# BBiQ-1_0.net
KiCad netlist of a schematic drawn in EAGLE
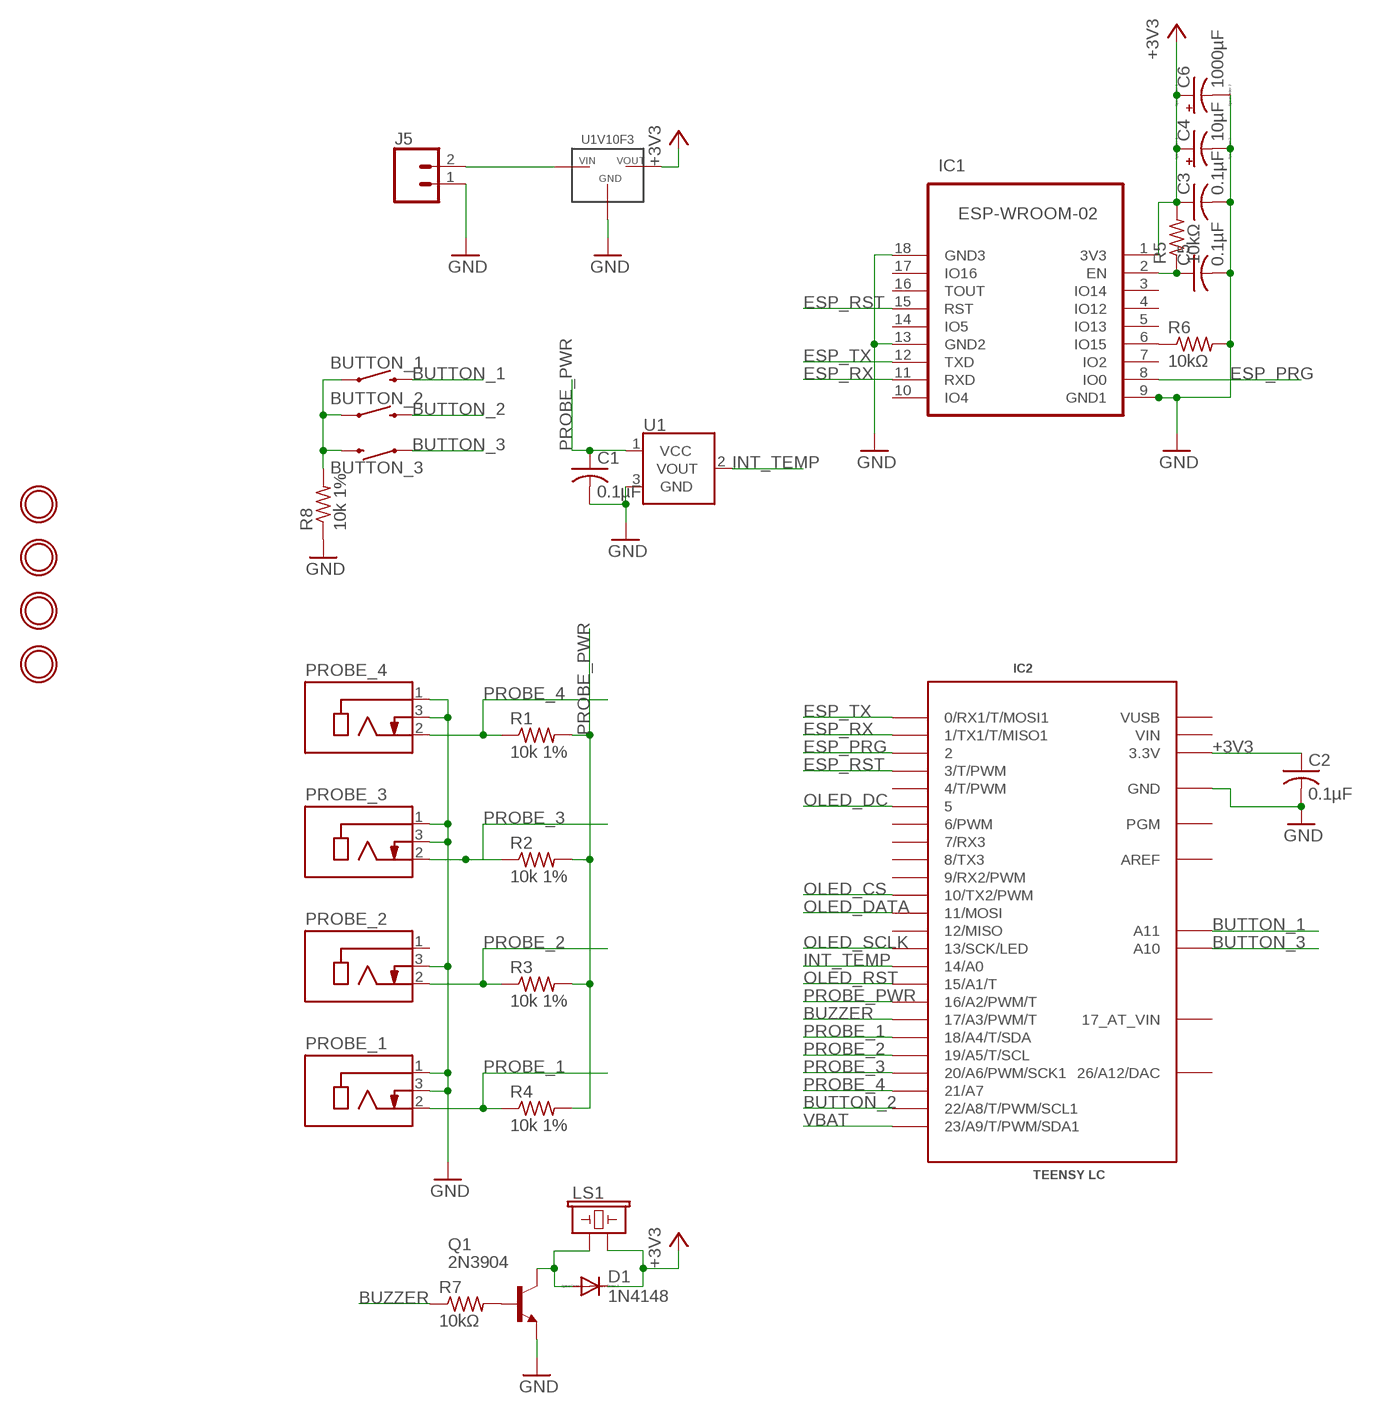
[diagram p0: schematic, sheet 1]

(export (version "E")
  (design (tool "Eeschema 10.0.6"))
  (components
    (comp (ref "BUTTON_1")
      (value "MOMENTARY-SWITCH-SPST-PTH-6.0MM")
      (footprint "eagle-import:TACTILE_SWITCH_PTH_6.0MM")
      (libsource (lib "eagle-import") (part "MOMENTARY-SWITCH-SPST-PTH-6.0MM"))
    )
    (comp (ref "BUTTON_2")
      (value "MOMENTARY-SWITCH-SPST-PTH-6.0MM")
      (footprint "eagle-import:TACTILE_SWITCH_PTH_6.0MM")
      (libsource (lib "eagle-import") (part "MOMENTARY-SWITCH-SPST-PTH-6.0MM"))
    )
    (comp (ref "BUTTON_3")
      (value "MOMENTARY-SWITCH-SPST-PTH-6.0MM")
      (footprint "eagle-import:TACTILE_SWITCH_PTH_6.0MM")
      (libsource (lib "eagle-import") (part "MOMENTARY-SWITCH-SPST-PTH-6.0MM"))
    )
    (comp (ref "C1")
      (value "0.1µF")
      (footprint "eagle-import:C025-025X050")
      (libsource (lib "eagle-import") (part "C-US025-025X050"))
    )
    (comp (ref "C2")
      (value "0.1µF")
      (footprint "eagle-import:C025-025X050")
      (libsource (lib "eagle-import") (part "C-US025-025X050"))
    )
    (comp (ref "C3")
      (value "0.1µF")
      (footprint "eagle-import:C025-025X050")
      (libsource (lib "eagle-import") (part "C-US025-025X050"))
    )
    (comp (ref "C4")
      (value "10µF")
      (footprint "eagle-import:E2-5")
      (libsource (lib "eagle-import") (part "CPOL-USE2-5"))
    )
    (comp (ref "C5")
      (value "0.1µF")
      (footprint "eagle-import:C025-025X050")
      (libsource (lib "eagle-import") (part "C-US025-025X050"))
    )
    (comp (ref "C6")
      (value "1000µF")
      (footprint "eagle-import:E3,5-8")
      (libsource (lib "eagle-import") (part "CPOL-USE3.5-8"))
    )
    (comp (ref "D1")
      (value "1N4148")
      (footprint "eagle-import:DO35-7")
      (libsource (lib "eagle-import") (part "1N4148DO35-7"))
    )
    (comp (ref "IC1")
      (value "ESP-WROOM-02")
      (footprint "eagle-import:ESP-WROOM-02")
      (libsource (lib "eagle-import") (part "ESP-WROOM-02"))
    )
    (comp (ref "IC2")
      (value "TEENSY LC")
      (footprint "eagle-import:TEENSY_3.0-3.2&LC_ALL_PINS")
      (libsource (lib "eagle-import") (part "TEENSY_LC_ALL_PINS"))
    )
    (comp (ref "J5")
      (value "CONN_02JST-PTH-2")
      (footprint "eagle-import:JST-2-PTH")
      (libsource (lib "eagle-import") (part "CONN_02JST-PTH-2"))
    )
    (comp (ref "LS1")
      (value "BUZZER-PTH")
      (footprint "eagle-import:BUZZER-12MM")
      (libsource (lib "eagle-import") (part "BUZZER-PTH"))
    )
    (comp (ref "PROBE_1")
      (value "MJ-2506N")
      (footprint "eagle-import:CUI_MJ-2506N")
      (fields (field (name "MANUFACTURER") "CUI INC"))
      (libsource (lib "eagle-import") (part "MJ-2506N"))
    )
    (comp (ref "PROBE_2")
      (value "MJ-2506N")
      (footprint "eagle-import:CUI_MJ-2506N")
      (fields (field (name "MANUFACTURER") "CUI INC"))
      (libsource (lib "eagle-import") (part "MJ-2506N"))
    )
    (comp (ref "PROBE_3")
      (value "MJ-2506N")
      (footprint "eagle-import:CUI_MJ-2506N")
      (fields (field (name "MANUFACTURER") "CUI INC"))
      (libsource (lib "eagle-import") (part "MJ-2506N"))
    )
    (comp (ref "PROBE_4")
      (value "MJ-2506N")
      (footprint "eagle-import:CUI_MJ-2506N")
      (fields (field (name "MANUFACTURER") "CUI INC"))
      (libsource (lib "eagle-import") (part "MJ-2506N"))
    )
    (comp (ref "Q1")
      (value "2N3904")
      (footprint "eagle-import:TO92")
      (libsource (lib "eagle-import") (part "2N3904"))
    )
    (comp (ref "R1")
      (value "10k 1%")
      (footprint "eagle-import:0207_7")
      (libsource (lib "eagle-import") (part "R-US_0207/7"))
    )
    (comp (ref "R2")
      (value "10k 1%")
      (footprint "eagle-import:0207_7")
      (libsource (lib "eagle-import") (part "R-US_0207/7"))
    )
    (comp (ref "R3")
      (value "10k 1%")
      (footprint "eagle-import:0207_7")
      (libsource (lib "eagle-import") (part "R-US_0207/7"))
    )
    (comp (ref "R4")
      (value "10k 1%")
      (footprint "eagle-import:0207_7")
      (libsource (lib "eagle-import") (part "R-US_0207/7"))
    )
    (comp (ref "R5")
      (value "10kΩ")
      (footprint "eagle-import:0207_7")
      (libsource (lib "eagle-import") (part "R-US_0207/7"))
    )
    (comp (ref "R6")
      (value "10kΩ")
      (footprint "eagle-import:0207_7")
      (libsource (lib "eagle-import") (part "R-US_0207/7"))
    )
    (comp (ref "R7")
      (value "10kΩ")
      (footprint "eagle-import:0207_7")
      (libsource (lib "eagle-import") (part "R-US_0207/7"))
    )
    (comp (ref "R8")
      (value "10k 1%")
      (footprint "eagle-import:0207_7")
      (libsource (lib "eagle-import") (part "R-US_0207/7"))
    )
    (comp (ref "U$2")
      (value "U1V10F3")
      (footprint "eagle-import:U1V10F3")
      (libsource (lib "eagle-import") (part "U1V10F3"))
    )
    (comp (ref "U$3")
      (value "MOUNTINGHOLE2.5")
      (footprint "eagle-import:MOUNTINGHOLE_2.5_PLATED")
      (libsource (lib "eagle-import") (part "MOUNTINGHOLE2.5"))
    )
    (comp (ref "U$4")
      (value "MOUNTINGHOLE2.5")
      (footprint "eagle-import:MOUNTINGHOLE_2.5_PLATED")
      (libsource (lib "eagle-import") (part "MOUNTINGHOLE2.5"))
    )
    (comp (ref "U$5")
      (value "MOUNTINGHOLE2.5")
      (footprint "eagle-import:MOUNTINGHOLE_2.5_PLATED")
      (libsource (lib "eagle-import") (part "MOUNTINGHOLE2.5"))
    )
    (comp (ref "U$6")
      (value "MOUNTINGHOLE2.5")
      (footprint "eagle-import:MOUNTINGHOLE_2.5_PLATED")
      (libsource (lib "eagle-import") (part "MOUNTINGHOLE2.5"))
    )
    (comp (ref "U1")
      (value "TMP36GT9")
      (footprint "eagle-import:TO-92")
      (libsource (lib "eagle-import") (part "TMP36GT9"))
    )
  )
  (nets
    (net (code "1") (name "+3V3") (class "Default")
      (node (ref "C2") (pin "1") (pinfunction "1_1") (pintype "passive"))
      (node (ref "C3") (pin "1") (pinfunction "1_1") (pintype "passive"))
      (node (ref "C4") (pin "+") (pinfunction "+_+") (pintype "passive"))
      (node (ref "C6") (pin "+") (pinfunction "+_+") (pintype "passive"))
      (node (ref "D1") (pin "C") (pinfunction "C_C") (pintype "passive"))
      (node (ref "IC1") (pin "1") (pinfunction "3V3_1") (pintype "power_in"))
      (node (ref "IC2") (pin "3.3V") (pinfunction "3.3V_3.3V") (pintype "power_in"))
      (node (ref "IC2") (pin "3.3V1") (pinfunction "3.3V_3.3V1") (pintype "power_in"))
      (node (ref "LS1") (pin "-") (pinfunction "2_-") (pintype "passive"))
      (node (ref "R5") (pin "2") (pinfunction "2_2") (pintype "passive"))
      (node (ref "U$2") (pin "VOUT") (pinfunction "VOUT_VOUT") (pintype "bidirectional"))
    )
    (net (code "2") (name "/26{slash}A12{slash}DAC") (class "Default")
      (node (ref "IC2") (pin "RESET/DAC") (pinfunction "26/A12/DAC_RESET/DAC") (pintype "power_in"))
    )
    (net (code "3") (name "/AREF") (class "Default")
      (node (ref "IC2") (pin "AREF") (pinfunction "AREF_AREF") (pintype "power_in"))
    )
    (net (code "4") (name "/BUTTON_1") (class "Default")
      (node (ref "BUTTON_1") (pin "3") (pinfunction "2_3") (pintype "passive"))
      (node (ref "IC2") (pin "A11") (pinfunction "A11_A11") (pintype "bidirectional"))
    )
    (net (code "5") (name "/BUTTON_2") (class "Default")
      (node (ref "BUTTON_2") (pin "3") (pinfunction "2_3") (pintype "passive"))
      (node (ref "IC2") (pin "22/A8") (pinfunction "22/A8/T/PWM/SCL1_22/A8") (pintype "bidirectional"))
    )
    (net (code "6") (name "/BUTTON_3") (class "Default")
      (node (ref "BUTTON_3") (pin "1") (pinfunction "1_1") (pintype "passive"))
      (node (ref "IC2") (pin "A10") (pinfunction "A10_A10") (pintype "bidirectional"))
    )
    (net (code "7") (name "/BUZZER") (class "Default")
      (node (ref "IC2") (pin "17/A3") (pinfunction "17/A3/PWM/T_17/A3") (pintype "bidirectional"))
      (node (ref "R7") (pin "1") (pinfunction "1_1") (pintype "passive"))
    )
    (net (code "8") (name "/ESP_PRG") (class "Default")
      (node (ref "IC1") (pin "8") (pinfunction "IO0_8") (pintype "bidirectional"))
      (node (ref "IC2") (pin "2") (pinfunction "2_2") (pintype "bidirectional"))
    )
    (net (code "9") (name "/ESP_RST") (class "Default")
      (node (ref "IC1") (pin "15") (pinfunction "RST_15") (pintype "bidirectional"))
      (node (ref "IC2") (pin "3") (pinfunction "3/T/PWM_3") (pintype "bidirectional"))
    )
    (net (code "10") (name "/ESP_RX") (class "Default")
      (node (ref "IC1") (pin "11") (pinfunction "RXD_11") (pintype "bidirectional"))
      (node (ref "IC2") (pin "1") (pinfunction "1/TX1/T/MISO1_1") (pintype "bidirectional"))
    )
    (net (code "11") (name "/ESP_TX") (class "Default")
      (node (ref "IC1") (pin "12") (pinfunction "TXD_12") (pintype "bidirectional"))
      (node (ref "IC2") (pin "0") (pinfunction "0/RX1/T/MOSI1_0") (pintype "bidirectional"))
    )
    (net (code "12") (name "/INT_TEMP") (class "Default")
      (node (ref "IC2") (pin "14/A0") (pinfunction "14/A0_14/A0") (pintype "bidirectional"))
      (node (ref "U1") (pin "2") (pinfunction "VOUT_2") (pintype "bidirectional"))
    )
    (net (code "13") (name "/OLED_CS") (class "Default")
      (node (ref "IC2") (pin "10") (pinfunction "10/TX2/PWM_10") (pintype "bidirectional"))
    )
    (net (code "14") (name "/OLED_DATA") (class "Default")
      (node (ref "IC2") (pin "11") (pinfunction "11/MOSI_11") (pintype "bidirectional"))
    )
    (net (code "15") (name "/OLED_DC") (class "Default")
      (node (ref "IC2") (pin "5") (pinfunction "5_5") (pintype "bidirectional"))
    )
    (net (code "16") (name "/OLED_RST") (class "Default")
      (node (ref "IC2") (pin "15/A1") (pinfunction "15/A1/T_15/A1") (pintype "bidirectional"))
    )
    (net (code "17") (name "/OLED_SCLK") (class "Default")
      (node (ref "IC2") (pin "13") (pinfunction "13/SCK/LED_13") (pintype "bidirectional"))
    )
    (net (code "18") (name "/PROBE_1") (class "Default")
      (node (ref "IC2") (pin "18/A4") (pinfunction "18/A4/T/SDA_18/A4") (pintype "bidirectional"))
      (node (ref "PROBE_1") (pin "2") (pinfunction "2_2") (pintype "passive"))
      (node (ref "R4") (pin "1") (pinfunction "1_1") (pintype "passive"))
    )
    (net (code "19") (name "/PROBE_2") (class "Default")
      (node (ref "IC2") (pin "19/A5") (pinfunction "19/A5/T/SCL_19/A5") (pintype "bidirectional"))
      (node (ref "PROBE_2") (pin "2") (pinfunction "2_2") (pintype "passive"))
      (node (ref "R3") (pin "1") (pinfunction "1_1") (pintype "passive"))
    )
    (net (code "20") (name "/PROBE_3") (class "Default")
      (node (ref "IC2") (pin "20/A6") (pinfunction "20/A6/PWM/SCK1_20/A6") (pintype "bidirectional"))
      (node (ref "PROBE_3") (pin "2") (pinfunction "2_2") (pintype "passive"))
      (node (ref "R2") (pin "1") (pinfunction "1_1") (pintype "passive"))
    )
    (net (code "21") (name "/PROBE_4") (class "Default")
      (node (ref "IC2") (pin "21/A7") (pinfunction "21/A7_21/A7") (pintype "bidirectional"))
      (node (ref "PROBE_4") (pin "2") (pinfunction "2_2") (pintype "passive"))
      (node (ref "R1") (pin "1") (pinfunction "1_1") (pintype "passive"))
    )
    (net (code "22") (name "/PROBE_PWR") (class "Default")
      (node (ref "C1") (pin "1") (pinfunction "1_1") (pintype "passive"))
      (node (ref "IC2") (pin "16/A2") (pinfunction "16/A2/PWM/T_16/A2") (pintype "bidirectional"))
      (node (ref "R1") (pin "2") (pinfunction "2_2") (pintype "passive"))
      (node (ref "R2") (pin "2") (pinfunction "2_2") (pintype "passive"))
      (node (ref "R3") (pin "2") (pinfunction "2_2") (pintype "passive"))
      (node (ref "R4") (pin "2") (pinfunction "2_2") (pintype "passive"))
      (node (ref "U1") (pin "1") (pinfunction "VCC_1") (pintype "bidirectional"))
    )
    (net (code "23") (name "/VBAT") (class "Default")
      (node (ref "IC2") (pin "23/A9") (pinfunction "23/A9/T/PWM/SDA1_23/A9") (pintype "bidirectional"))
      (node (ref "J5") (pin "2") (pinfunction "2_2") (pintype "passive"))
      (node (ref "U$2") (pin "VIN") (pinfunction "VIN_VIN") (pintype "bidirectional"))
    )
    (net (code "24") (name "/VIN") (class "Default")
      (node (ref "IC2") (pin "VIN") (pinfunction "VIN_VIN") (pintype "power_in"))
    )
    (net (code "25") (name "/VUSB") (class "Default")
      (node (ref "IC2") (pin "VUSB") (pinfunction "VUSB_VUSB") (pintype "power_in"))
    )
    (net (code "26") (name "GND") (class "Default")
      (node (ref "C1") (pin "2") (pinfunction "2_2") (pintype "passive"))
      (node (ref "C2") (pin "2") (pinfunction "2_2") (pintype "passive"))
      (node (ref "C3") (pin "2") (pinfunction "2_2") (pintype "passive"))
      (node (ref "C4") (pin "-") (pinfunction "-_-") (pintype "passive"))
      (node (ref "C5") (pin "2") (pinfunction "2_2") (pintype "passive"))
      (node (ref "C6") (pin "-") (pinfunction "-_-") (pintype "passive"))
      (node (ref "IC1") (pin "13") (pinfunction "GND2_13") (pintype "power_in"))
      (node (ref "IC1") (pin "18") (pinfunction "GND3_18") (pintype "power_in"))
      (node (ref "IC1") (pin "19") (pinfunction "GND0_19") (pintype "power_in"))
      (node (ref "IC1") (pin "9") (pinfunction "GND1_9") (pintype "power_in"))
      (node (ref "IC2") (pin "AGND") (pinfunction "GND_AGND") (pintype "power_in"))
      (node (ref "IC2") (pin "GND") (pinfunction "GND_GND") (pintype "power_in"))
      (node (ref "IC2") (pin "GND1") (pinfunction "GND_GND1") (pintype "power_in"))
      (node (ref "J5") (pin "1") (pinfunction "1_1") (pintype "passive"))
      (node (ref "PROBE_1") (pin "1") (pinfunction "1_1") (pintype "passive"))
      (node (ref "PROBE_1") (pin "3") (pinfunction "3_3") (pintype "passive"))
      (node (ref "PROBE_2") (pin "3") (pinfunction "3_3") (pintype "passive"))
      (node (ref "PROBE_3") (pin "1") (pinfunction "1_1") (pintype "passive"))
      (node (ref "PROBE_3") (pin "3") (pinfunction "3_3") (pintype "passive"))
      (node (ref "PROBE_4") (pin "1") (pinfunction "1_1") (pintype "passive"))
      (node (ref "PROBE_4") (pin "3") (pinfunction "3_3") (pintype "passive"))
      (node (ref "Q1") (pin "3") (pinfunction "E_3") (pintype "passive"))
      (node (ref "R6") (pin "2") (pinfunction "2_2") (pintype "passive"))
      (node (ref "R8") (pin "1") (pinfunction "1_1") (pintype "passive"))
      (node (ref "U$2") (pin "GND") (pinfunction "GND_GND") (pintype "bidirectional"))
      (node (ref "U1") (pin "3") (pinfunction "GND_3") (pintype "bidirectional"))
    )
    (net (code "27") (name "Net-(BUTTON_3-2)") (class "Default")
      (node (ref "BUTTON_1") (pin "1") (pinfunction "1_1") (pintype "passive"))
      (node (ref "BUTTON_2") (pin "1") (pinfunction "1_1") (pintype "passive"))
      (node (ref "BUTTON_3") (pin "3") (pinfunction "2_3") (pintype "passive"))
      (node (ref "R8") (pin "2") (pinfunction "2_2") (pintype "passive"))
    )
    (net (code "28") (name "Net-(IC1-EN)") (class "Default")
      (node (ref "C5") (pin "1") (pinfunction "1_1") (pintype "passive"))
      (node (ref "IC1") (pin "2") (pinfunction "EN_2") (pintype "bidirectional"))
      (node (ref "R5") (pin "1") (pinfunction "1_1") (pintype "passive"))
    )
    (net (code "29") (name "Net-(IC1-IO15)") (class "Default")
      (node (ref "IC1") (pin "6") (pinfunction "IO15_6") (pintype "bidirectional"))
      (node (ref "R6") (pin "1") (pinfunction "1_1") (pintype "passive"))
    )
    (net (code "30") (name "Net-(LS1-1)") (class "Default")
      (node (ref "D1") (pin "A") (pinfunction "A_A") (pintype "passive"))
      (node (ref "LS1") (pin "+") (pinfunction "1_+") (pintype "passive"))
      (node (ref "Q1") (pin "1") (pinfunction "C_1") (pintype "passive"))
    )
    (net (code "31") (name "Net-(Q1-B)") (class "Default")
      (node (ref "Q1") (pin "2") (pinfunction "B_2") (pintype "passive"))
      (node (ref "R7") (pin "2") (pinfunction "2_2") (pintype "passive"))
    )
    (net (code "32") (name "unconnected-(IC1-IO2-Pad7)") (class "Default")
      (node (ref "IC1") (pin "7") (pinfunction "IO2_7") (pintype "bidirectional"))
    )
    (net (code "33") (name "unconnected-(IC1-IO4-Pad10)") (class "Default")
      (node (ref "IC1") (pin "10") (pinfunction "IO4_10") (pintype "bidirectional"))
    )
    (net (code "34") (name "unconnected-(IC1-IO5-Pad14)") (class "Default")
      (node (ref "IC1") (pin "14") (pinfunction "IO5_14") (pintype "open_collector"))
    )
    (net (code "35") (name "unconnected-(IC1-IO12-Pad4)") (class "Default")
      (node (ref "IC1") (pin "4") (pinfunction "IO12_4") (pintype "bidirectional"))
    )
    (net (code "36") (name "unconnected-(IC1-IO13-Pad5)") (class "Default")
      (node (ref "IC1") (pin "5") (pinfunction "IO13_5") (pintype "bidirectional"))
    )
    (net (code "37") (name "unconnected-(IC1-IO14-Pad3)") (class "Default")
      (node (ref "IC1") (pin "3") (pinfunction "IO14_3") (pintype "bidirectional"))
    )
    (net (code "38") (name "unconnected-(IC1-IO16-Pad17)") (class "Default")
      (node (ref "IC1") (pin "17") (pinfunction "IO16_17") (pintype "bidirectional"))
    )
    (net (code "39") (name "unconnected-(IC1-TOUT-Pad16)") (class "Default")
      (node (ref "IC1") (pin "16") (pinfunction "TOUT_16") (pintype "bidirectional"))
    )
    (net (code "40") (name "unconnected-(IC2-4{slash}T{slash}PWM-Pad4)") (class "Default")
      (node (ref "IC2") (pin "4") (pinfunction "4/T/PWM_4") (pintype "bidirectional"))
    )
    (net (code "41") (name "unconnected-(IC2-6{slash}PWM-Pad6)") (class "Default")
      (node (ref "IC2") (pin "6") (pinfunction "6/PWM_6") (pintype "bidirectional"))
    )
    (net (code "42") (name "unconnected-(IC2-7{slash}RX3-Pad7)") (class "Default")
      (node (ref "IC2") (pin "7") (pinfunction "7/RX3_7") (pintype "bidirectional"))
    )
    (net (code "43") (name "unconnected-(IC2-8{slash}TX3-Pad8)") (class "Default")
      (node (ref "IC2") (pin "8") (pinfunction "8/TX3_8") (pintype "bidirectional"))
    )
    (net (code "44") (name "unconnected-(IC2-9{slash}RX2{slash}PWM-Pad9)") (class "Default")
      (node (ref "IC2") (pin "9") (pinfunction "9/RX2/PWM_9") (pintype "bidirectional"))
    )
    (net (code "45") (name "unconnected-(IC2-12{slash}MISO-Pad12)") (class "Default")
      (node (ref "IC2") (pin "12") (pinfunction "12/MISO_12") (pintype "bidirectional"))
    )
    (net (code "46") (name "unconnected-(IC2-17_AT_VIN-PadVBAT)") (class "Default")
      (node (ref "IC2") (pin "VBAT") (pinfunction "17_AT_VIN_VBAT") (pintype "bidirectional"))
    )
    (net (code "47") (name "unconnected-(IC2-PadPGM)") (class "Default")
      (node (ref "IC2") (pin "PGM") (pinfunction "PGM_PGM") (pintype "bidirectional"))
    )
    (net (code "48") (name "unconnected-(PROBE_2-Pad1)") (class "Default")
      (node (ref "PROBE_2") (pin "1") (pinfunction "1_1") (pintype "passive"))
    )
  )
)
